# Sheet2.net
KiCad netlist of a schematic drawn in Altium Designer
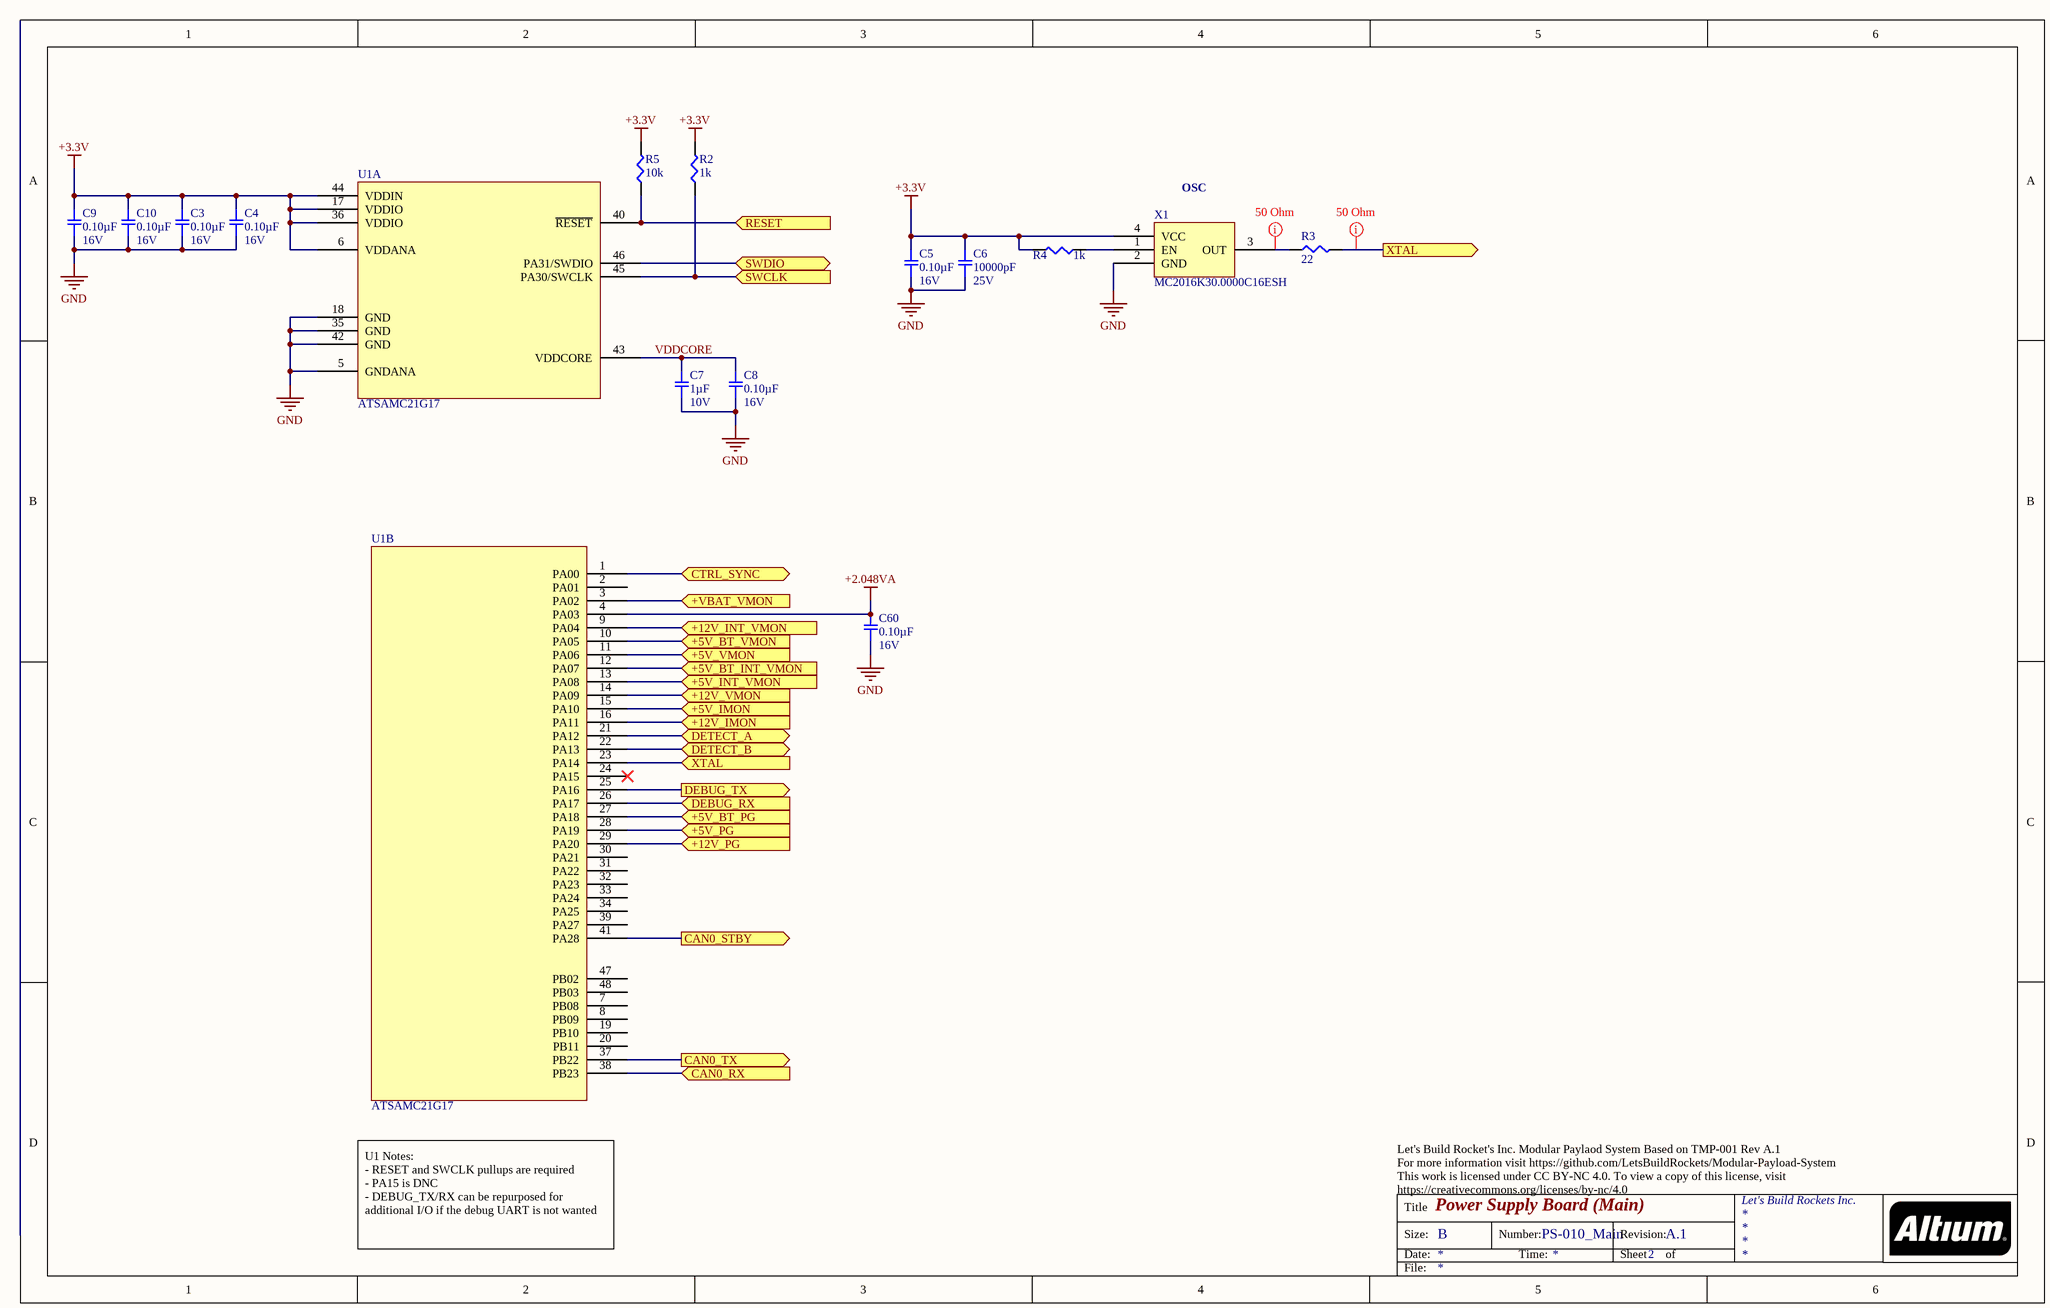
[diagram p0: Sheet2.SchDoc]

(export (version "E")
  (design (tool "Eeschema 10.0.6"))
  (components
    (comp (ref "C3")
      (value "0.10µF")
      (footprint "SMD-0402C")
      (description "CAP CER 0.1UF 16V X7R 0402")
      (fields
        (field (name "DIGI-KEY PART NUMBER") "490-4759-1-ND")
        (field (name "PART NUMBER") "GCM155R71C104KA55D")
        (field (name "VOLTAGE") "16V")
      )
      (libsource (lib "capacitor_murata_0402") (part "GCM155R71C104KA55D"))
    )
    (comp (ref "C4")
      (value "0.10µF")
      (footprint "SMD-0402C")
      (description "CAP CER 0.1UF 16V X7R 0402")
      (fields
        (field (name "DIGI-KEY PART NUMBER") "490-4759-1-ND")
        (field (name "PART NUMBER") "GCM155R71C104KA55D")
        (field (name "VOLTAGE") "16V")
      )
      (libsource (lib "capacitor_murata_0402") (part "GCM155R71C104KA55D"))
    )
    (comp (ref "C5")
      (value "0.10µF")
      (footprint "SMD-0402C")
      (description "CAP CER 0.1UF 16V X7R 0402")
      (fields
        (field (name "DIGI-KEY PART NUMBER") "490-4759-1-ND")
        (field (name "PART NUMBER") "GCM155R71C104KA55D")
        (field (name "VOLTAGE") "16V")
      )
      (libsource (lib "capacitor_murata_0402") (part "GCM155R71C104KA55D"))
    )
    (comp (ref "C6")
      (value "10000pF")
      (footprint "SMD-0402C")
      (description "CAP CER 10000PF 25V X7R 0402")
      (fields
        (field (name "DIGI-KEY PART NUMBER") "490-6043-1-ND")
        (field (name "PART NUMBER") "GCM155R71E103KA37D")
        (field (name "VOLTAGE") "25V")
      )
      (libsource (lib "capacitor_murata_0402") (part "GCM155R71E103KA37D"))
    )
    (comp (ref "C7")
      (value "1µF")
      (footprint "SMD-0402C")
      (description "CAP CER 1UF 10V X7S 0402")
      (fields
        (field (name "DIGI-KEY PART NUMBER") "490-13409-1-ND")
        (field (name "PART NUMBER") "GCM155C71A105KE38D")
        (field (name "VOLTAGE") "10V")
      )
      (libsource (lib "capacitor_murata_0402") (part "GCM155C71A105KE38D"))
    )
    (comp (ref "C8")
      (value "0.10µF")
      (footprint "SMD-0402C")
      (description "CAP CER 0.1UF 16V X7R 0402")
      (fields
        (field (name "DIGI-KEY PART NUMBER") "490-4759-1-ND")
        (field (name "PART NUMBER") "GCM155R71C104KA55D")
        (field (name "VOLTAGE") "16V")
      )
      (libsource (lib "capacitor_murata_0402") (part "GCM155R71C104KA55D"))
    )
    (comp (ref "C9")
      (value "0.10µF")
      (footprint "SMD-0402C")
      (description "CAP CER 0.1UF 16V X7R 0402")
      (fields
        (field (name "DIGI-KEY PART NUMBER") "490-4759-1-ND")
        (field (name "PART NUMBER") "GCM155R71C104KA55D")
        (field (name "VOLTAGE") "16V")
      )
      (libsource (lib "capacitor_murata_0402") (part "GCM155R71C104KA55D"))
    )
    (comp (ref "C10")
      (value "0.10µF")
      (footprint "SMD-0402C")
      (description "CAP CER 0.1UF 16V X7R 0402")
      (fields
        (field (name "DIGI-KEY PART NUMBER") "490-4759-1-ND")
        (field (name "PART NUMBER") "GCM155R71C104KA55D")
        (field (name "VOLTAGE") "16V")
      )
      (libsource (lib "capacitor_murata_0402") (part "GCM155R71C104KA55D"))
    )
    (comp (ref "C60")
      (value "0.10µF")
      (footprint "SMD-0402C")
      (description "CAP CER 0.1UF 16V X7R 0402")
      (fields
        (field (name "DIGI-KEY PART NUMBER") "490-4759-1-ND")
        (field (name "PART NUMBER") "GCM155R71C104KA55D")
        (field (name "VOLTAGE") "16V")
      )
      (libsource (lib "capacitor_murata_0402") (part "GCM155R71C104KA55D"))
    )
    (comp (ref "R2")
      (value "1k")
      (footprint "SMD-0402-RES")
      (description "RES SMD 1K OHM 5% 1/10W 0402")
      (fields (field (name "PART NUMBER") "ERJ-2GEJ102X") (field (name "DIGI-KEY PART NUMBER") "P1.0KJCT-ND"))
      (libsource (lib "Panasonic_ERJ_0402") (part "ERJ-2GEJ102X"))
    )
    (comp (ref "R3")
      (value "22")
      (footprint "SMD-0402-RES")
      (description "RES SMD 22 OHM 1% 1/10W 0402")
      (fields
        (field (name "PART NUMBER") "ERJ-2RKF22R0X")
        (field (name "DIGI-KEY PART NUMBER") "P22.0LCT-ND")
      )
      (libsource (lib "Panasonic_ERJ_0402") (part "ERJ-2RKF22R0X"))
    )
    (comp (ref "R4")
      (value "1k")
      (footprint "SMD-0402-RES")
      (description "RES SMD 1K OHM 5% 1/10W 0402")
      (fields (field (name "PART NUMBER") "ERJ-2GEJ102X") (field (name "DIGI-KEY PART NUMBER") "P1.0KJCT-ND"))
      (libsource (lib "Panasonic_ERJ_0402") (part "ERJ-2GEJ102X"))
    )
    (comp (ref "R5")
      (value "10k")
      (footprint "SMD-0402-RES")
      (description "RES SMD 10K OHM 5% 1/10W 0402")
      (fields (field (name "PART NUMBER") "ERJ-2GEJ103X") (field (name "DIGI-KEY PART NUMBER") "P10KJCT-ND"))
      (libsource (lib "Panasonic_ERJ_0402") (part "ERJ-2GEJ103X"))
    )
    (comp (ref "U1")
      (value "ATSAMC21G17")
      (footprint "TSQFP50P900X900X120-48N")
      (libsource (lib "ModularPayload") (part "ATSAMC21G17"))
    )
    (comp (ref "X1")
      (value "MC2016K30.0000C16ESH")
      (footprint "MC2016")
      (libsource (lib "ModularPayload") (part "MC2016K30.0000C16ESH"))
    )
  )
  (nets
    (net (code "1") (name "+2.048VA") (class "Default")
      (node (ref "C60") (pin "2") (pinfunction "2_2") (pintype "passive"))
      (node (ref "U1") (pin "4") (pinfunction "PA03_4") (pintype "passive"))
    )
    (net (code "2") (name "+3.3V") (class "Default")
      (node (ref "C10") (pin "2") (pinfunction "2_2") (pintype "passive"))
      (node (ref "C3") (pin "2") (pinfunction "2_2") (pintype "passive"))
      (node (ref "C4") (pin "2") (pinfunction "2_2") (pintype "passive"))
      (node (ref "C5") (pin "2") (pinfunction "2_2") (pintype "passive"))
      (node (ref "C6") (pin "2") (pinfunction "2_2") (pintype "passive"))
      (node (ref "C9") (pin "2") (pinfunction "2_2") (pintype "passive"))
      (node (ref "R2") (pin "2") (pinfunction "2_2") (pintype "passive"))
      (node (ref "R4") (pin "2") (pinfunction "2_2") (pintype "passive"))
      (node (ref "R5") (pin "2") (pinfunction "2_2") (pintype "passive"))
      (node (ref "U1") (pin "17") (pinfunction "VDDIO_17") (pintype "passive"))
      (node (ref "U1") (pin "36") (pinfunction "VDDIO_36") (pintype "passive"))
      (node (ref "U1") (pin "44") (pinfunction "VDDIN_44") (pintype "passive"))
      (node (ref "U1") (pin "6") (pinfunction "VDDANA_6") (pintype "passive"))
      (node (ref "X1") (pin "4") (pinfunction "VCC_4") (pintype "passive"))
    )
    (net (code "3") (name "/+5V_BT_INT_VMON") (class "Default")
      (node (ref "U1") (pin "12") (pinfunction "PA07_12") (pintype "passive"))
    )
    (net (code "4") (name "/+5V_BT_PG") (class "Default")
      (node (ref "U1") (pin "27") (pinfunction "PA18_27") (pintype "passive"))
    )
    (net (code "5") (name "/+5V_BT_VMON") (class "Default")
      (node (ref "U1") (pin "10") (pinfunction "PA05_10") (pintype "passive"))
    )
    (net (code "6") (name "/+5V_IMON") (class "Default")
      (node (ref "U1") (pin "15") (pinfunction "PA10_15") (pintype "passive"))
    )
    (net (code "7") (name "/+5V_INT_VMON") (class "Default")
      (node (ref "U1") (pin "13") (pinfunction "PA08_13") (pintype "passive"))
    )
    (net (code "8") (name "/+5V_PG") (class "Default")
      (node (ref "U1") (pin "28") (pinfunction "PA19_28") (pintype "passive"))
    )
    (net (code "9") (name "/+5V_VMON") (class "Default")
      (node (ref "U1") (pin "11") (pinfunction "PA06_11") (pintype "passive"))
    )
    (net (code "10") (name "/+12V_IMON") (class "Default")
      (node (ref "U1") (pin "16") (pinfunction "PA11_16") (pintype "passive"))
    )
    (net (code "11") (name "/+12V_INT_VMON") (class "Default")
      (node (ref "U1") (pin "9") (pinfunction "PA04_9") (pintype "passive"))
    )
    (net (code "12") (name "/+12V_PG") (class "Default")
      (node (ref "U1") (pin "29") (pinfunction "PA20_29") (pintype "passive"))
    )
    (net (code "13") (name "/+12V_VMON") (class "Default")
      (node (ref "U1") (pin "14") (pinfunction "PA09_14") (pintype "passive"))
    )
    (net (code "14") (name "/+VBAT_VMON") (class "Default")
      (node (ref "U1") (pin "3") (pinfunction "PA02_3") (pintype "passive"))
    )
    (net (code "15") (name "/CAN0_RX") (class "Default")
      (node (ref "U1") (pin "38") (pinfunction "PB23_38") (pintype "passive"))
    )
    (net (code "16") (name "/CAN0_STBY") (class "Default")
      (node (ref "U1") (pin "41") (pinfunction "PA28_41") (pintype "passive"))
    )
    (net (code "17") (name "/CAN0_TX") (class "Default")
      (node (ref "U1") (pin "37") (pinfunction "PB22_37") (pintype "passive"))
    )
    (net (code "18") (name "/CTRL_SYNC") (class "Default")
      (node (ref "U1") (pin "1") (pinfunction "PA00_1") (pintype "passive"))
    )
    (net (code "19") (name "/DEBUG_RX") (class "Default")
      (node (ref "U1") (pin "26") (pinfunction "PA17_26") (pintype "passive"))
    )
    (net (code "20") (name "/DEBUG_TX") (class "Default")
      (node (ref "U1") (pin "25") (pinfunction "PA16_25") (pintype "passive"))
    )
    (net (code "21") (name "/DETECT_A") (class "Default")
      (node (ref "U1") (pin "21") (pinfunction "PA12_21") (pintype "passive"))
    )
    (net (code "22") (name "/DETECT_B") (class "Default")
      (node (ref "U1") (pin "22") (pinfunction "PA13_22") (pintype "passive"))
    )
    (net (code "23") (name "/RESET") (class "Default")
      (node (ref "R5") (pin "1") (pinfunction "1_1") (pintype "passive"))
      (node (ref "U1") (pin "40") (pinfunction "~{RESET}_40") (pintype "passive"))
    )
    (net (code "24") (name "/SWCLK") (class "Default")
      (node (ref "R2") (pin "1") (pinfunction "1_1") (pintype "passive"))
      (node (ref "U1") (pin "45") (pinfunction "PA30/SWCLK_45") (pintype "passive"))
    )
    (net (code "25") (name "/SWDIO") (class "Default")
      (node (ref "U1") (pin "46") (pinfunction "PA31/SWDIO_46") (pintype "passive"))
    )
    (net (code "26") (name "/VDDCORE") (class "Default")
      (node (ref "C7") (pin "2") (pinfunction "2_2") (pintype "passive"))
      (node (ref "C8") (pin "2") (pinfunction "2_2") (pintype "passive"))
      (node (ref "U1") (pin "43") (pinfunction "VDDCORE_43") (pintype "passive"))
    )
    (net (code "27") (name "/XTAL") (class "Default")
      (node (ref "R3") (pin "2") (pinfunction "2_2") (pintype "passive"))
      (node (ref "U1") (pin "23") (pinfunction "PA14_23") (pintype "passive"))
    )
    (net (code "28") (name "GND") (class "Default")
      (node (ref "C10") (pin "1") (pinfunction "1_1") (pintype "passive"))
      (node (ref "C3") (pin "1") (pinfunction "1_1") (pintype "passive"))
      (node (ref "C4") (pin "1") (pinfunction "1_1") (pintype "passive"))
      (node (ref "C5") (pin "1") (pinfunction "1_1") (pintype "passive"))
      (node (ref "C6") (pin "1") (pinfunction "1_1") (pintype "passive"))
      (node (ref "C60") (pin "1") (pinfunction "1_1") (pintype "passive"))
      (node (ref "C7") (pin "1") (pinfunction "1_1") (pintype "passive"))
      (node (ref "C8") (pin "1") (pinfunction "1_1") (pintype "passive"))
      (node (ref "C9") (pin "1") (pinfunction "1_1") (pintype "passive"))
      (node (ref "U1") (pin "18") (pinfunction "GND_18") (pintype "passive"))
      (node (ref "U1") (pin "35") (pinfunction "GND_35") (pintype "passive"))
      (node (ref "U1") (pin "42") (pinfunction "GND_42") (pintype "passive"))
      (node (ref "U1") (pin "5") (pinfunction "GNDANA_5") (pintype "passive"))
      (node (ref "X1") (pin "2") (pinfunction "GND_2") (pintype "passive"))
    )
    (net (code "29") (name "Net-(X1-EN)") (class "Default")
      (node (ref "R4") (pin "1") (pinfunction "1_1") (pintype "passive"))
      (node (ref "X1") (pin "1") (pinfunction "EN_1") (pintype "passive"))
    )
    (net (code "30") (name "Net-(X1-OUT)") (class "Default")
      (node (ref "R3") (pin "1") (pinfunction "1_1") (pintype "passive"))
      (node (ref "X1") (pin "3") (pinfunction "OUT_3") (pintype "passive"))
    )
    (net (code "31") (name "unconnected-(U1B-PA01-Pad2)") (class "Default")
      (node (ref "U1") (pin "2") (pinfunction "PA01_2") (pintype "passive"))
    )
    (net (code "32") (name "unconnected-(U1B-PA15-Pad24)") (class "Default")
      (node (ref "U1") (pin "24") (pinfunction "PA15_24") (pintype "passive+no_connect"))
    )
    (net (code "33") (name "unconnected-(U1B-PA21-Pad30)") (class "Default")
      (node (ref "U1") (pin "30") (pinfunction "PA21_30") (pintype "passive"))
    )
    (net (code "34") (name "unconnected-(U1B-PA22-Pad31)") (class "Default")
      (node (ref "U1") (pin "31") (pinfunction "PA22_31") (pintype "passive"))
    )
    (net (code "35") (name "unconnected-(U1B-PA23-Pad32)") (class "Default")
      (node (ref "U1") (pin "32") (pinfunction "PA23_32") (pintype "passive"))
    )
    (net (code "36") (name "unconnected-(U1B-PA24-Pad33)") (class "Default")
      (node (ref "U1") (pin "33") (pinfunction "PA24_33") (pintype "passive"))
    )
    (net (code "37") (name "unconnected-(U1B-PA25-Pad34)") (class "Default")
      (node (ref "U1") (pin "34") (pinfunction "PA25_34") (pintype "passive"))
    )
    (net (code "38") (name "unconnected-(U1B-PA27-Pad39)") (class "Default")
      (node (ref "U1") (pin "39") (pinfunction "PA27_39") (pintype "passive"))
    )
    (net (code "39") (name "unconnected-(U1B-PB02-Pad47)") (class "Default")
      (node (ref "U1") (pin "47") (pinfunction "PB02_47") (pintype "passive"))
    )
    (net (code "40") (name "unconnected-(U1B-PB03-Pad48)") (class "Default")
      (node (ref "U1") (pin "48") (pinfunction "PB03_48") (pintype "passive"))
    )
    (net (code "41") (name "unconnected-(U1B-PB08-Pad7)") (class "Default")
      (node (ref "U1") (pin "7") (pinfunction "PB08_7") (pintype "passive"))
    )
    (net (code "42") (name "unconnected-(U1B-PB09-Pad8)") (class "Default")
      (node (ref "U1") (pin "8") (pinfunction "PB09_8") (pintype "passive"))
    )
    (net (code "43") (name "unconnected-(U1B-PB10-Pad19)") (class "Default")
      (node (ref "U1") (pin "19") (pinfunction "PB10_19") (pintype "passive"))
    )
    (net (code "44") (name "unconnected-(U1B-PB11-Pad20)") (class "Default")
      (node (ref "U1") (pin "20") (pinfunction "PB11_20") (pintype "passive"))
    )
  )
)
